# 1_-_MCU.net
KiCad netlist of a schematic drawn in Altium Designer
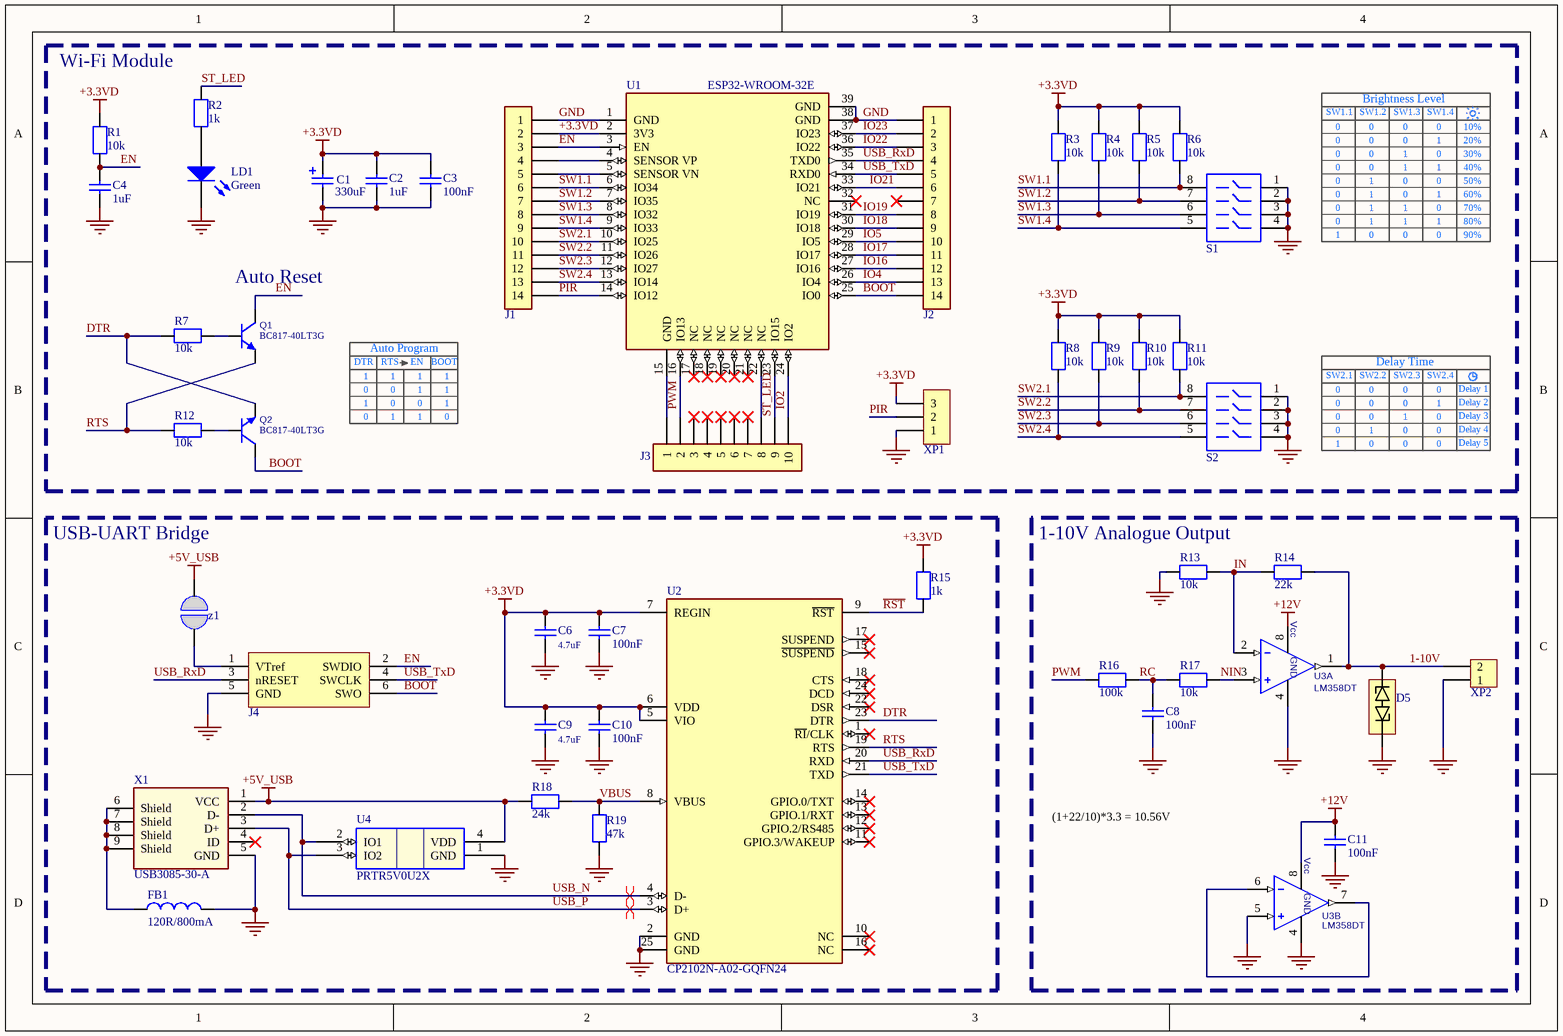
[diagram p0: [1] - MCU.SchDoc]

(export (version "E")
  (design (tool "Eeschema 10.0.6"))
  (components
    (comp (ref "C1")
      (value "330uF")
      (footprint "TANT CAP CASE B")
      (description "Surface Mount Tantalum Capacitor, 330 µF, 6.3 V, 1411 [3528 Metric], ± 20%, 0.8 ohm, B")
      (fields (field (name "TOLERANCE") "+/-20%") (field (name "MANUFACTURER") "KEMET"))
      (libsource (lib "YAQF") (part "Capacitors_SMD_TANT"))
    )
    (comp (ref "C2")
      (value "1uF")
      (footprint "CC0603")
      (description "SMD Multilayer Ceramic Capacitor, 1 µF, 16 V, 0603 [1608 Metric], ± 10%, X7R, MC")
      (fields
        (field (name "MANUFACTURER") "MULTICOMP")
        (field (name "MANUFACTURER PART NUMBER") "MC0603B105K160CT")
      )
      (libsource (lib "YAQF") (part "Capacitors_SMD"))
    )
    (comp (ref "C3")
      (value "100nF")
      (footprint "CC0603")
      (description "SMD Multilayer Ceramic Capacitor, 0.1 µF, 16 V, 0603 [1608 Metric], ± 10%, X7R, MC")
      (fields
        (field (name "MANUFACTURER") "MULTICOMP")
        (field (name "MANUFACTURER PART NUMBER") "MC0603B104K160CT")
      )
      (libsource (lib "YAQF") (part "Capacitors_SMD"))
    )
    (comp (ref "C4")
      (value "1uF")
      (footprint "CC0603")
      (description "SMD Multilayer Ceramic Capacitor, 1 µF, 16 V, 0603 [1608 Metric], ± 10%, X7R, MC")
      (fields
        (field (name "MANUFACTURER") "MULTICOMP")
        (field (name "MANUFACTURER PART NUMBER") "MC0603B105K160CT")
      )
      (libsource (lib "YAQF") (part "Capacitors_SMD"))
    )
    (comp (ref "C6")
      (value "4.7uF")
      (footprint "CC0603")
      (description "SMD Multilayer Ceramic Capacitor, 4.7 µF, 6.3 V, 0603 [1608 Metric], ± 10%, X7R, CL")
      (fields
        (field (name "MANUFACTURER") "SAMSUNG ELECTRO-MECHANICS")
        (field (name "MANUFACTURER PART NUMBER") "CL10B475KQ8NQNC")
      )
      (libsource (lib "ENEL004.201.001") (part "Capacitors_SMD_10"))
    )
    (comp (ref "C7")
      (value "100nF")
      (footprint "CC0603")
      (description "SMD Multilayer Ceramic Capacitor, 0.1 µF, 16 V, 0603 [1608 Metric], ± 10%, X7R, MC")
      (fields
        (field (name "MANUFACTURER") "MULTICOMP")
        (field (name "MANUFACTURER PART NUMBER") "MC0603B104K160CT")
      )
      (libsource (lib "YAQF") (part "Capacitors_SMD"))
    )
    (comp (ref "C8")
      (value "100nF")
      (footprint "CC0603")
      (description "SMD Multilayer Ceramic Capacitor, 0.1 µF, 16 V, 0603 [1608 Metric], ± 10%, X7R, MC")
      (fields
        (field (name "MANUFACTURER") "MULTICOMP")
        (field (name "MANUFACTURER PART NUMBER") "MC0603B104K160CT")
      )
      (libsource (lib "YAQF") (part "Capacitors_SMD"))
    )
    (comp (ref "C9")
      (value "4.7uF")
      (footprint "CC0603")
      (description "SMD Multilayer Ceramic Capacitor, 4.7 µF, 6.3 V, 0603 [1608 Metric], ± 10%, X7R, CL")
      (fields
        (field (name "MANUFACTURER") "SAMSUNG ELECTRO-MECHANICS")
        (field (name "MANUFACTURER PART NUMBER") "CL10B475KQ8NQNC")
      )
      (libsource (lib "ENEL004.201.001") (part "Capacitors_SMD_10"))
    )
    (comp (ref "C10")
      (value "100nF")
      (footprint "CC0603")
      (description "SMD Multilayer Ceramic Capacitor, 0.1 µF, 16 V, 0603 [1608 Metric], ± 10%, X7R, MC")
      (fields
        (field (name "MANUFACTURER") "MULTICOMP")
        (field (name "MANUFACTURER PART NUMBER") "MC0603B104K160CT")
      )
      (libsource (lib "YAQF") (part "Capacitors_SMD"))
    )
    (comp (ref "C11")
      (value "100nF")
      (footprint "CC0603")
      (description "SMD Multilayer Ceramic Capacitor, 0.1 µF, 16 V, 0603 [1608 Metric], ± 10%, X7R, MC")
      (fields
        (field (name "MANUFACTURER") "MULTICOMP")
        (field (name "MANUFACTURER PART NUMBER") "MC0603B104K160CT")
      )
      (libsource (lib "YAQF") (part "Capacitors_SMD"))
    )
    (comp (ref "D5")
      (value "CDSOD323-T12SC")
      (footprint "SOD323")
      (description "TVS DIODE 12VWM 29.5VC SOD323")
      (fields
        (field (name "VOLTAGE") "12V")
        (field (name "MANUFACTURER") "Bourns")
        (field (name "PUBLISHER") "dlehkobyt")
      )
      (libsource (lib "Aldiva_Altium_Library") (part "PESDXVL1BA"))
    )
    (comp (ref "FB1")
      (value "120R/800mA")
      (footprint "ind0603")
      (description "Ferrite Bead, 0603 [1608 Metric], 120 ohm, 800 mA, BLM18AG, 0.18 ohm, ± 25%")
      (fields
        (field (name "MANUFACTURER") "Murata Electronics")
        (field (name "MANUFACTURER PART NUMBER") "BLM18AG121BH1D")
      )
      (libsource (lib "YAQF") (part "Inductor_SMD"))
    )
    (comp (ref "J1")
      (value "TMS-114-02-L-S")
      (footprint "1-10V_PIR_V1.0:TMS-114-YY-XX-S")
      (description "Pin Header, Vertical, Board-to-Board, 1.27 mm, 1 Rows, 14 Contacts, Through Hole, TMS")
      (fields (field (name "MANUFACTURER") "SAMTEC") (field (name "MOUSER PART NUMBER") "200-TMS11402LS"))
      (libsource (lib "1-10V_PIR_V1.0") (part "TMS-114-02-L-S"))
    )
    (comp (ref "J2")
      (value "TMS-114-02-L-S")
      (footprint "1-10V_PIR_V1.0:TMS-114-YY-XX-S")
      (description "Pin Header, Vertical, Board-to-Board, 1.27 mm, 1 Rows, 14 Contacts, Through Hole, TMS")
      (fields (field (name "MANUFACTURER") "SAMTEC") (field (name "MOUSER PART NUMBER") "200-TMS11402LS"))
      (libsource (lib "") (part "TMS-114-02-L-S_1"))
    )
    (comp (ref "J3")
      (value "TMS-110-02-L-S")
      (footprint "SAMTEC_TMS-110-02-L-S")
      (description "Pin Header, Vertical, Board-to-Board, 1.27 mm, 1 Rows, 10 Contacts, Through Hole, TMS")
      (fields (field (name "MANUFACTURER") "SAMTEC"))
      (libsource (lib "1-10V_PIR_V1.0") (part "TMS-110-02-L-S"))
    )
    (comp (ref "J4")
      (value "TC2030-IDC")
      (footprint "TC2030-IDC")
      (description "TC2030-IDC 6-Pin Tag-Connect Plug-of-Nails™ Spring-Pin Cable with Legs")
      (libsource (lib "1-10V_PIR_V1.0") (part "TC2030-IDC"))
    )
    (comp (ref "LD1")
      (value "LED")
      (footprint "LED0603")
      (description "LED GREEN 0603 SMD")
      (fields
        (field (name "PART NUMBER") "TLMG1100-GS08")
        (field (name "COLOR") "Green")
        (field (name "VOLTAGE") "2.1V")
        (field (name "PUBLISHER") "asavchenko")
      )
      (libsource (lib "Aldiva_Altium_Library") (part "LED"))
    )
    (comp (ref "Q1")
      (value "BC817-40LT3G")
      (footprint "SOT23-3")
      (description "TRANS NPN 45V 0.5A SOT23")
      (fields (field (name "PART NUMBER") "BC817-40LT3G") (field (name "MANUFACTURER") "ONS, NXP"))
      (libsource (lib "Aldiva_Altium_Library") (part "NPN_transistor_SOT23-3"))
    )
    (comp (ref "Q2")
      (value "BC817-40LT3G")
      (footprint "SOT23-3")
      (description "TRANS NPN 45V 0.5A SOT23")
      (fields (field (name "PART NUMBER") "BC817-40LT3G") (field (name "MANUFACTURER") "ONS, NXP"))
      (libsource (lib "Aldiva_Altium_Library") (part "NPN_transistor_SOT23-3"))
    )
    (comp (ref "R1")
      (value "10k")
      (footprint "RC0603")
      (description "SMD Chip Resistor, 10 kohm, ± 1%, 100 mW, 0603 [1608 Metric], Thick Film, General Purpose")
      (fields
        (field (name "MANUFACTURER") "MULTICOMP")
        (field (name "MANUFACTURER PART NUMBER") "MCWR06X1002FTL")
      )
      (libsource (lib "") (part "Resistors_SMD_1"))
    )
    (comp (ref "R2")
      (value "1k")
      (footprint "RC0603")
      (description "SMD Chip Resistor, 1 kohm, ± 1%, 100 mW, 0603 [1608 Metric], Thick Film, General Purpose")
      (fields
        (field (name "MANUFACTURER") "MULTICOMP")
        (field (name "MANUFACTURER PART NUMBER") "MCWR06X1001FTL")
      )
      (libsource (lib "ENEL004.201.001") (part "Resistors_SMD"))
    )
    (comp (ref "R3")
      (value "10k")
      (footprint "RC0603")
      (description "SMD Chip Resistor, 10 kohm, ± 1%, 100 mW, 0603 [1608 Metric], Thick Film, General Purpose")
      (fields
        (field (name "MANUFACTURER") "MULTICOMP")
        (field (name "MANUFACTURER PART NUMBER") "MCWR06X1002FTL")
      )
      (libsource (lib "") (part "Resistors_SMD_1"))
    )
    (comp (ref "R4")
      (value "10k")
      (footprint "RC0603")
      (description "SMD Chip Resistor, 10 kohm, ± 1%, 100 mW, 0603 [1608 Metric], Thick Film, General Purpose")
      (fields
        (field (name "MANUFACTURER") "MULTICOMP")
        (field (name "MANUFACTURER PART NUMBER") "MCWR06X1002FTL")
      )
      (libsource (lib "") (part "Resistors_SMD_1"))
    )
    (comp (ref "R5")
      (value "10k")
      (footprint "RC0603")
      (description "SMD Chip Resistor, 10 kohm, ± 1%, 100 mW, 0603 [1608 Metric], Thick Film, General Purpose")
      (fields
        (field (name "MANUFACTURER") "MULTICOMP")
        (field (name "MANUFACTURER PART NUMBER") "MCWR06X1002FTL")
      )
      (libsource (lib "") (part "Resistors_SMD_1"))
    )
    (comp (ref "R6")
      (value "10k")
      (footprint "RC0603")
      (description "SMD Chip Resistor, 10 kohm, ± 1%, 100 mW, 0603 [1608 Metric], Thick Film, General Purpose")
      (fields
        (field (name "MANUFACTURER") "MULTICOMP")
        (field (name "MANUFACTURER PART NUMBER") "MCWR06X1002FTL")
      )
      (libsource (lib "") (part "Resistors_SMD_1"))
    )
    (comp (ref "R7")
      (value "10k")
      (footprint "RC0603")
      (description "SMD Chip Resistor, 10 kohm, ± 1%, 100 mW, 0603 [1608 Metric], Thick Film, General Purpose")
      (fields
        (field (name "MANUFACTURER") "MULTICOMP")
        (field (name "MANUFACTURER PART NUMBER") "MCWR06X1002FTL")
      )
      (libsource (lib "") (part "Resistors_SMD_2"))
    )
    (comp (ref "R8")
      (value "10k")
      (footprint "RC0603")
      (description "SMD Chip Resistor, 10 kohm, ± 1%, 100 mW, 0603 [1608 Metric], Thick Film, General Purpose")
      (fields
        (field (name "MANUFACTURER") "MULTICOMP")
        (field (name "MANUFACTURER PART NUMBER") "MCWR06X1002FTL")
      )
      (libsource (lib "") (part "Resistors_SMD_1"))
    )
    (comp (ref "R9")
      (value "10k")
      (footprint "RC0603")
      (description "SMD Chip Resistor, 10 kohm, ± 1%, 100 mW, 0603 [1608 Metric], Thick Film, General Purpose")
      (fields
        (field (name "MANUFACTURER") "MULTICOMP")
        (field (name "MANUFACTURER PART NUMBER") "MCWR06X1002FTL")
      )
      (libsource (lib "") (part "Resistors_SMD_1"))
    )
    (comp (ref "R10")
      (value "10k")
      (footprint "RC0603")
      (description "SMD Chip Resistor, 10 kohm, ± 1%, 100 mW, 0603 [1608 Metric], Thick Film, General Purpose")
      (fields
        (field (name "MANUFACTURER") "MULTICOMP")
        (field (name "MANUFACTURER PART NUMBER") "MCWR06X1002FTL")
      )
      (libsource (lib "") (part "Resistors_SMD_1"))
    )
    (comp (ref "R11")
      (value "10k")
      (footprint "RC0603")
      (description "SMD Chip Resistor, 10 kohm, ± 1%, 100 mW, 0603 [1608 Metric], Thick Film, General Purpose")
      (fields
        (field (name "MANUFACTURER") "MULTICOMP")
        (field (name "MANUFACTURER PART NUMBER") "MCWR06X1002FTL")
      )
      (libsource (lib "") (part "Resistors_SMD_1"))
    )
    (comp (ref "R12")
      (value "10k")
      (footprint "RC0603")
      (description "SMD Chip Resistor, 10 kohm, ± 1%, 100 mW, 0603 [1608 Metric], Thick Film, General Purpose")
      (fields
        (field (name "MANUFACTURER") "MULTICOMP")
        (field (name "MANUFACTURER PART NUMBER") "MCWR06X1002FTL")
      )
      (libsource (lib "") (part "Resistors_SMD_2"))
    )
    (comp (ref "R13")
      (value "10k")
      (footprint "RC0603")
      (description "SMD Chip Resistor, 10 kohm, ± 1%, 100 mW, 0603 [1608 Metric], Thick Film, General Purpose")
      (fields
        (field (name "MANUFACTURER") "MULTICOMP")
        (field (name "MANUFACTURER PART NUMBER") "MCWR06X1002FTL")
      )
      (libsource (lib "YAQF") (part "Resistors_SMD"))
    )
    (comp (ref "R14")
      (value "22k")
      (footprint "RC0603")
      (description "SMD Chip Resistor, 22 kohm, ± 1%, 100 mW, 0603 [1608 Metric], Thick Film, General Purpose")
      (fields
        (field (name "MANUFACTURER") "MULTICOMP")
        (field (name "MANUFACTURER PART NUMBER") "MCWR06X2202FTL")
      )
      (libsource (lib "YAQF") (part "Resistors_SMD"))
    )
    (comp (ref "R15")
      (value "1k")
      (footprint "RC0603")
      (description "SMD Chip Resistor, 1 kohm, ± 1%, 100 mW, 0603 [1608 Metric], Thick Film, General Purpose")
      (fields
        (field (name "MANUFACTURER") "MULTICOMP")
        (field (name "MANUFACTURER PART NUMBER") "MCWR06X1001FTL")
      )
      (libsource (lib "ENEL004.201.001") (part "Resistors_SMD"))
    )
    (comp (ref "R16")
      (value "100k")
      (footprint "RC0603")
      (description "SMD Chip Resistor, 100 kohm, ± 1%, 100 mW, 0603 [1608 Metric], Thick Film, General Purpose")
      (fields
        (field (name "MANUFACTURER") "MULTICOMP")
        (field (name "MANUFACTURER PART NUMBER") "MCWR06X1003FTL")
      )
      (libsource (lib "ENEL004.201.001") (part "Resistors_SMD_4"))
    )
    (comp (ref "R17")
      (value "10k")
      (footprint "RC0603")
      (description "SMD Chip Resistor, 10 kohm, ± 1%, 100 mW, 0603 [1608 Metric], Thick Film, General Purpose")
      (fields
        (field (name "MANUFACTURER") "MULTICOMP")
        (field (name "MANUFACTURER PART NUMBER") "MCWR06X1002FTL")
      )
      (libsource (lib "") (part "Resistors_SMD_2"))
    )
    (comp (ref "R18")
      (value "24k")
      (footprint "RC0603")
      (description "SMD Chip Resistor, 24 kohm, ± 1%, 100 mW, 0603 [1608 Metric], Thick Film, General Purpose")
      (fields
        (field (name "MANUFACTURER") "MULTICOMP")
        (field (name "MANUFACTURER PART NUMBER") "MCWR06X2402FTL")
      )
      (libsource (lib "") (part "Resistors_SMD_24_1"))
    )
    (comp (ref "R19")
      (value "47k")
      (footprint "RC0603")
      (description "SMD Chip Resistor, 47 kohm, ± 1%, 100 mW, 0603 [1608 Metric], Thick Film, General Purpose")
      (fields
        (field (name "MANUFACTURER") "MULTICOMP")
        (field (name "MANUFACTURER PART NUMBER") "MCWR06X4702FTL")
      )
      (libsource (lib "ENEL004.201.001") (part "Resistors_SMD_24"))
    )
    (comp (ref "S1")
      (value "SW-DIP4")
      (footprint "SW-DIP-8")
      (description "DIP / SIP Switch, 4 Circuits, Raised Slide, Through Hole, SPST-NO, 24 V, 25 mA")
      (fields (field (name "PART NUMBER") "MCNDS-04V") (field (name "MANUFACTURER") "MULTICOMP PRO"))
      (libsource (lib "1-10V_PIR_V1.0") (part "SW-DIP4"))
    )
    (comp (ref "S2")
      (value "SW-DIP4")
      (footprint "SW-DIP-8")
      (description "DIP / SIP Switch, 4 Circuits, Raised Slide, Through Hole, SPST-NO, 24 V, 25 mA")
      (fields (field (name "PART NUMBER") "MCNDS-04V") (field (name "MANUFACTURER") "MULTICOMP PRO"))
      (libsource (lib "1-10V_PIR_V1.0") (part "SW-DIP4"))
    )
    (comp (ref "U1")
      (value "ESP32-WROOM-32E")
      (footprint "ESP32-WROOM-32E-Footprint-1")
      (fields
        (field (name "MANUFACTURER") "Espressif Systems")
        (field (name "MANUFACTURER PART NUMBER") "ESP32-WROOM-32E-N16")
      )
      (libsource (lib "1-10V_PIR_V1.0") (part "ESP32-WROOM-32E"))
    )
    (comp (ref "U2")
      (value "CP2102N-A02-GQFN24")
      (footprint "Components - 17.11.22 - 15.18:FP-CP2102N-A02-GQFN24-MFG")
      (description "IC USB TO UART BRIDGE QFN24")
      (fields (field (name "MANUFACTURER") "Silabs"))
      (libsource (lib "3PHPowerMeter_V1.0") (part "CMP-08107-000010-1"))
    )
    (comp (ref "U3")
      (value "LM358DT")
      (footprint "SO-8")
      (description "Operational Amplifier, Dual, 2 Amplifier, 1.1 MHz, 0.6 V/µs, 3V to 30V, SOIC, 8 Pins")
      (fields (field (name "MANUFACTURER") "STMICROELECTRONICS"))
      (libsource (lib "1-10V_PIR_V1.0") (part "LM358DT"))
    )
    (comp (ref "U4")
      (value "PRTR5V0U2X")
      (footprint "SOT190P230X110-4L")
      (description "ESD Protection Device, TVS, 7.5 V, SOT-143B, 4 Pins, 5.5 V, PRTR5")
      (fields (field (name "MANUFACTURER") "NXP Semiconductor"))
      (libsource (lib "YAQF") (part "PRTR5V0U2X_Protect"))
    )
    (comp (ref "X1")
      (value "USB3085-30-A")
      (footprint "USB3085-30-A")
      (description "USB Connector, Micro USB Type AB, USB 2.0, Receptacle, 5 Ways, Surface Mount, Right Angle")
      (fields (field (name "MANUFACTURER") "GTC"))
      (libsource (lib "1-10V_PIR_V1.0") (part "USB3085-30-A"))
    )
    (comp (ref "XP1")
      (value "Header 3x1pins")
      (footprint "MC 1,5_3-G-3,81")
      (description "Terminal Block, Header, 3.81 mm, 3 Ways, 8 A, 160 V, Through Hole Right Angle")
      (fields
        (field (name "PART NUMBER") "MC 1,5/ 3-G-3,81")
        (field (name "MANUFACTURER") "PHOENIX CONTACT")
        (field (name "PUBLISHER") "dlegkobyt")
      )
      (libsource (lib "Aldiva_Altium_Library") (part "Header 3x1pins"))
    )
    (comp (ref "XP2")
      (value "Header 2x1pins")
      (footprint "MC 1,5_2-G-3,81")
      (description "Terminal Block, Header, 3.81 mm, 2 Ways, 8 A, 160 V, Through Hole Right Angle")
      (fields
        (field (name "PART NUMBER") "MC 1,5/ 2-G-3,81")
        (field (name "MANUFACTURER") "PHOENIX CONTACT")
        (field (name "PUBLISHER") "dlegkobyt")
      )
      (libsource (lib "Aldiva_Altium_Library") (part "Header 2x1pins"))
    )
    (comp (ref "z1")
      (value "SHORT")
      (footprint "PAD_JUMPER")
      (libsource (lib "1-10V_PIR_V1.0") (part "JUMPER_OPEN"))
    )
  )
  (nets
    (net (code "1") (name "+3.3VD") (class "Default")
      (node (ref "C1") (pin "1") (pinfunction "1_1") (pintype "passive"))
      (node (ref "C10") (pin "1") (pinfunction "1_1") (pintype "passive"))
      (node (ref "C2") (pin "1") (pinfunction "1_1") (pintype "passive"))
      (node (ref "C3") (pin "1") (pinfunction "1_1") (pintype "passive"))
      (node (ref "C6") (pin "1") (pinfunction "1_1") (pintype "passive"))
      (node (ref "C7") (pin "1") (pinfunction "1_1") (pintype "passive"))
      (node (ref "C9") (pin "1") (pinfunction "1_1") (pintype "passive"))
      (node (ref "J1") (pin "2") (pinfunction "2_2") (pintype "passive"))
      (node (ref "R1") (pin "2") (pinfunction "2_2") (pintype "passive"))
      (node (ref "R10") (pin "2") (pinfunction "2_2") (pintype "passive"))
      (node (ref "R11") (pin "2") (pinfunction "2_2") (pintype "passive"))
      (node (ref "R15") (pin "2") (pinfunction "2_2") (pintype "passive"))
      (node (ref "R3") (pin "2") (pinfunction "2_2") (pintype "passive"))
      (node (ref "R4") (pin "2") (pinfunction "2_2") (pintype "passive"))
      (node (ref "R5") (pin "2") (pinfunction "2_2") (pintype "passive"))
      (node (ref "R6") (pin "2") (pinfunction "2_2") (pintype "passive"))
      (node (ref "R8") (pin "2") (pinfunction "2_2") (pintype "passive"))
      (node (ref "R9") (pin "2") (pinfunction "2_2") (pintype "passive"))
      (node (ref "U1") (pin "2") (pinfunction "3V3_2") (pintype "power_in"))
      (node (ref "U2") (pin "5") (pinfunction "VIO_5") (pintype "power_in"))
      (node (ref "U2") (pin "6") (pinfunction "VDD_6") (pintype "power_in"))
      (node (ref "U2") (pin "7") (pinfunction "REGIN_7") (pintype "power_in"))
      (node (ref "XP1") (pin "3") (pinfunction "3_3") (pintype "passive"))
    )
    (net (code "2") (name "+5V_USB") (class "Default")
      (node (ref "R18") (pin "2") (pinfunction "2_2") (pintype "passive"))
      (node (ref "U4") (pin "4") (pinfunction "VDD_4") (pintype "power_in"))
      (node (ref "X1") (pin "1") (pinfunction "VCC_1") (pintype "passive"))
      (node (ref "z1") (pin "1") (pintype "passive"))
    )
    (net (code "3") (name "+12V") (class "Default")
      (node (ref "C11") (pin "1") (pinfunction "1_1") (pintype "passive"))
      (node (ref "U3") (pin "8") (pinfunction "Vcc_8") (pintype "power_in"))
    )
    (net (code "4") (name "/1-10V") (class "Default")
      (node (ref "D5") (pin "1") (pinfunction "P1_1") (pintype "passive"))
      (node (ref "R14") (pin "2") (pinfunction "2_2") (pintype "passive"))
      (node (ref "U3") (pin "1") (pinfunction "OUT1_1") (pintype "output"))
      (node (ref "XP2") (pin "2") (pinfunction "2_2") (pintype "passive"))
    )
    (net (code "5") (name "/BOOT") (class "Default")
      (node (ref "J2") (pin "14") (pinfunction "14_14") (pintype "passive"))
      (node (ref "J4") (pin "6") (pinfunction "SWO_6") (pintype "passive"))
      (node (ref "Q2") (pin "3") (pinfunction "C_3") (pintype "passive"))
      (node (ref "U1") (pin "25") (pinfunction "IO0_25") (pintype "bidirectional"))
    )
    (net (code "6") (name "/DTR") (class "Default")
      (node (ref "Q2") (pin "2") (pinfunction "E_2") (pintype "passive"))
      (node (ref "R7") (pin "2") (pinfunction "2_2") (pintype "passive"))
      (node (ref "U2") (pin "23") (pinfunction "DTR_23") (pintype "output"))
    )
    (net (code "7") (name "/EN") (class "Default")
      (node (ref "C4") (pin "1") (pinfunction "1_1") (pintype "passive"))
      (node (ref "J1") (pin "3") (pinfunction "3_3") (pintype "passive"))
      (node (ref "J4") (pin "2") (pinfunction "SWDIO_2") (pintype "passive"))
      (node (ref "Q1") (pin "3") (pinfunction "C_3") (pintype "passive"))
      (node (ref "R1") (pin "1") (pinfunction "1_1") (pintype "passive"))
      (node (ref "U1") (pin "3") (pinfunction "EN_3") (pintype "input"))
    )
    (net (code "8") (name "/IN") (class "Default")
      (node (ref "R13") (pin "2") (pinfunction "2_2") (pintype "passive"))
      (node (ref "R14") (pin "1") (pinfunction "1_1") (pintype "passive"))
      (node (ref "U3") (pin "2") (pinfunction "IN1-_2") (pintype "input"))
    )
    (net (code "9") (name "/IO2") (class "Default")
      (node (ref "J3") (pin "10") (pinfunction "10_10") (pintype "passive"))
      (node (ref "U1") (pin "24") (pinfunction "IO2_24") (pintype "bidirectional"))
    )
    (net (code "10") (name "/IO4") (class "Default")
      (node (ref "J2") (pin "13") (pinfunction "13_13") (pintype "passive"))
      (node (ref "U1") (pin "26") (pinfunction "IO4_26") (pintype "bidirectional"))
    )
    (net (code "11") (name "/IO5") (class "Default")
      (node (ref "J2") (pin "10") (pinfunction "10_10") (pintype "passive"))
      (node (ref "U1") (pin "29") (pinfunction "IO5_29") (pintype "bidirectional"))
    )
    (net (code "12") (name "/IO16") (class "Default")
      (node (ref "J2") (pin "12") (pinfunction "12_12") (pintype "passive"))
      (node (ref "U1") (pin "27") (pinfunction "IO16_27") (pintype "bidirectional"))
    )
    (net (code "13") (name "/IO17") (class "Default")
      (node (ref "J2") (pin "11") (pinfunction "11_11") (pintype "passive"))
      (node (ref "U1") (pin "28") (pinfunction "IO17_28") (pintype "bidirectional"))
    )
    (net (code "14") (name "/IO18") (class "Default")
      (node (ref "J2") (pin "9") (pinfunction "9_9") (pintype "passive"))
      (node (ref "U1") (pin "30") (pinfunction "IO18_30") (pintype "bidirectional"))
    )
    (net (code "15") (name "/IO19") (class "Default")
      (node (ref "J2") (pin "8") (pinfunction "8_8") (pintype "passive"))
      (node (ref "U1") (pin "31") (pinfunction "IO19_31") (pintype "bidirectional"))
    )
    (net (code "16") (name "/IO21") (class "Default")
      (node (ref "J2") (pin "6") (pinfunction "6_6") (pintype "passive"))
      (node (ref "U1") (pin "33") (pinfunction "IO21_33") (pintype "bidirectional"))
    )
    (net (code "17") (name "/IO22") (class "Default")
      (node (ref "J2") (pin "3") (pinfunction "3_3") (pintype "passive"))
      (node (ref "U1") (pin "36") (pinfunction "IO22_36") (pintype "bidirectional"))
    )
    (net (code "18") (name "/IO23") (class "Default")
      (node (ref "J2") (pin "2") (pinfunction "2_2") (pintype "passive"))
      (node (ref "U1") (pin "37") (pinfunction "IO23_37") (pintype "bidirectional"))
    )
    (net (code "19") (name "/NIN") (class "Default")
      (node (ref "R17") (pin "1") (pinfunction "1_1") (pintype "passive"))
      (node (ref "U3") (pin "3") (pinfunction "IN1+_3") (pintype "input"))
    )
    (net (code "20") (name "/PIR") (class "Default")
      (node (ref "J1") (pin "14") (pinfunction "14_14") (pintype "passive"))
      (node (ref "U1") (pin "14") (pinfunction "IO12_14") (pintype "bidirectional"))
      (node (ref "XP1") (pin "2") (pinfunction "2_2") (pintype "passive"))
    )
    (net (code "21") (name "/PWM") (class "Default")
      (node (ref "J3") (pin "2") (pinfunction "2_2") (pintype "passive"))
      (node (ref "R16") (pin "1") (pinfunction "1_1") (pintype "passive"))
      (node (ref "U1") (pin "16") (pinfunction "IO13_16") (pintype "bidirectional"))
    )
    (net (code "22") (name "/RC") (class "Default")
      (node (ref "C8") (pin "1") (pinfunction "1_1") (pintype "passive"))
      (node (ref "R16") (pin "2") (pinfunction "2_2") (pintype "passive"))
      (node (ref "R17") (pin "2") (pinfunction "2_2") (pintype "passive"))
    )
    (net (code "23") (name "/RTS") (class "Default")
      (node (ref "Q1") (pin "2") (pinfunction "E_2") (pintype "passive"))
      (node (ref "R12") (pin "2") (pinfunction "2_2") (pintype "passive"))
      (node (ref "U2") (pin "19") (pinfunction "RTS_19") (pintype "output"))
    )
    (net (code "24") (name "/ST_LED") (class "Default")
      (node (ref "J3") (pin "9") (pinfunction "9_9") (pintype "passive"))
      (node (ref "R2") (pin "2") (pinfunction "2_2") (pintype "passive"))
      (node (ref "U1") (pin "23") (pinfunction "IO15_23") (pintype "bidirectional"))
    )
    (net (code "25") (name "/SW1.1") (class "Default")
      (node (ref "J1") (pin "6") (pinfunction "6_6") (pintype "passive"))
      (node (ref "R6") (pin "1") (pinfunction "1_1") (pintype "passive"))
      (node (ref "S1") (pin "8") (pinfunction "8_8") (pintype "passive"))
      (node (ref "U1") (pin "6") (pinfunction "IO34_6") (pintype "bidirectional"))
    )
    (net (code "26") (name "/SW1.2") (class "Default")
      (node (ref "J1") (pin "7") (pinfunction "7_7") (pintype "passive"))
      (node (ref "R5") (pin "1") (pinfunction "1_1") (pintype "passive"))
      (node (ref "S1") (pin "7") (pinfunction "7_7") (pintype "passive"))
      (node (ref "U1") (pin "7") (pinfunction "IO35_7") (pintype "bidirectional"))
    )
    (net (code "27") (name "/SW1.3") (class "Default")
      (node (ref "J1") (pin "8") (pinfunction "8_8") (pintype "passive"))
      (node (ref "R4") (pin "1") (pinfunction "1_1") (pintype "passive"))
      (node (ref "S1") (pin "6") (pinfunction "6_6") (pintype "passive"))
      (node (ref "U1") (pin "8") (pinfunction "IO32_8") (pintype "bidirectional"))
    )
    (net (code "28") (name "/SW1.4") (class "Default")
      (node (ref "J1") (pin "9") (pinfunction "9_9") (pintype "passive"))
      (node (ref "R3") (pin "1") (pinfunction "1_1") (pintype "passive"))
      (node (ref "S1") (pin "5") (pinfunction "5_5") (pintype "passive"))
      (node (ref "U1") (pin "9") (pinfunction "IO33_9") (pintype "bidirectional"))
    )
    (net (code "29") (name "/SW2.1") (class "Default")
      (node (ref "J1") (pin "10") (pinfunction "10_10") (pintype "passive"))
      (node (ref "R11") (pin "1") (pinfunction "1_1") (pintype "passive"))
      (node (ref "S2") (pin "8") (pinfunction "8_8") (pintype "passive"))
      (node (ref "U1") (pin "10") (pinfunction "IO25_10") (pintype "bidirectional"))
    )
    (net (code "30") (name "/SW2.2") (class "Default")
      (node (ref "J1") (pin "11") (pinfunction "11_11") (pintype "passive"))
      (node (ref "R10") (pin "1") (pinfunction "1_1") (pintype "passive"))
      (node (ref "S2") (pin "7") (pinfunction "7_7") (pintype "passive"))
      (node (ref "U1") (pin "11") (pinfunction "IO26_11") (pintype "bidirectional"))
    )
    (net (code "31") (name "/SW2.3") (class "Default")
      (node (ref "J1") (pin "12") (pinfunction "12_12") (pintype "passive"))
      (node (ref "R9") (pin "1") (pinfunction "1_1") (pintype "passive"))
      (node (ref "S2") (pin "6") (pinfunction "6_6") (pintype "passive"))
      (node (ref "U1") (pin "12") (pinfunction "IO27_12") (pintype "bidirectional"))
    )
    (net (code "32") (name "/SW2.4") (class "Default")
      (node (ref "J1") (pin "13") (pinfunction "13_13") (pintype "passive"))
      (node (ref "R8") (pin "1") (pinfunction "1_1") (pintype "passive"))
      (node (ref "S2") (pin "5") (pinfunction "5_5") (pintype "passive"))
      (node (ref "U1") (pin "13") (pinfunction "IO14_13") (pintype "bidirectional"))
    )
    (net (code "33") (name "/USB_N") (class "Default")
      (node (ref "U2") (pin "4") (pinfunction "D-_4") (pintype "bidirectional"))
      (node (ref "U4") (pin "2") (pinfunction "IO1_2") (pintype "bidirectional"))
      (node (ref "X1") (pin "2") (pinfunction "D-_2") (pintype "passive"))
    )
    (net (code "34") (name "/USB_P") (class "Default")
      (node (ref "U2") (pin "3") (pinfunction "D+_3") (pintype "bidirectional"))
      (node (ref "U4") (pin "3") (pinfunction "IO2_3") (pintype "bidirectional"))
      (node (ref "X1") (pin "3") (pinfunction "D+_3") (pintype "passive"))
    )
    (net (code "35") (name "/USB_RxD") (class "Default")
      (node (ref "J2") (pin "4") (pinfunction "4_4") (pintype "passive"))
      (node (ref "J4") (pin "3") (pinfunction "nRESET_3") (pintype "passive"))
      (node (ref "U1") (pin "35") (pinfunction "TXD0_35") (pintype "output"))
      (node (ref "U2") (pin "20") (pinfunction "RXD_20") (pintype "input"))
    )
    (net (code "36") (name "/USB_TxD") (class "Default")
      (node (ref "J2") (pin "5") (pinfunction "5_5") (pintype "passive"))
      (node (ref "J4") (pin "4") (pinfunction "SWCLK_4") (pintype "passive"))
      (node (ref "U1") (pin "34") (pinfunction "RXD0_34") (pintype "input"))
      (node (ref "U2") (pin "21") (pinfunction "TXD_21") (pintype "output"))
    )
    (net (code "37") (name "/VBUS") (class "Default")
      (node (ref "R18") (pin "1") (pinfunction "1_1") (pintype "passive"))
      (node (ref "R19") (pin "2") (pinfunction "2_2") (pintype "passive"))
      (node (ref "U2") (pin "8") (pinfunction "VBUS_8") (pintype "input"))
    )
    (net (code "38") (name "/~{RST}") (class "Default")
      (node (ref "R15") (pin "1") (pinfunction "1_1") (pintype "passive"))
      (node (ref "U2") (pin "9") (pinfunction "~{RST}_9") (pintype "passive"))
    )
    (net (code "39") (name "GND") (class "Default")
      (node (ref "C1") (pin "2") (pinfunction "2_2") (pintype "passive"))
      (node (ref "C10") (pin "2") (pinfunction "2_2") (pintype "passive"))
      (node (ref "C11") (pin "2") (pinfunction "2_2") (pintype "passive"))
      (node (ref "C2") (pin "2") (pinfunction "2_2") (pintype "passive"))
      (node (ref "C3") (pin "2") (pinfunction "2_2") (pintype "passive"))
      (node (ref "C4") (pin "2") (pinfunction "2_2") (pintype "passive"))
      (node (ref "C6") (pin "2") (pinfunction "2_2") (pintype "passive"))
      (node (ref "C7") (pin "2") (pinfunction "2_2") (pintype "passive"))
      (node (ref "C8") (pin "2") (pinfunction "2_2") (pintype "passive"))
      (node (ref "C9") (pin "2") (pinfunction "2_2") (pintype "passive"))
      (node (ref "D5") (pin "2") (pinfunction "P2_2") (pintype "passive"))
      (node (ref "FB1") (pin "1") (pinfunction "1_1") (pintype "passive"))
      (node (ref "J1") (pin "1") (pinfunction "1_1") (pintype "passive"))
      (node (ref "J2") (pin "1") (pinfunction "1_1") (pintype "passive"))
      (node (ref "J4") (pin "5") (pinfunction "GND_5") (pintype "passive"))
      (node (ref "LD1") (pin "1") (pinfunction "K_1") (pintype "passive"))
      (node (ref "R13") (pin "1") (pinfunction "1_1") (pintype "passive"))
      (node (ref "R19") (pin "1") (pinfunction "1_1") (pintype "passive"))
      (node (ref "S1") (pin "1") (pinfunction "1_1") (pintype "passive"))
      (node (ref "S1") (pin "2") (pinfunction "2_2") (pintype "passive"))
      (node (ref "S1") (pin "3") (pinfunction "3_3") (pintype "passive"))
      (node (ref "S1") (pin "4") (pinfunction "4_4") (pintype "passive"))
      (node (ref "S2") (pin "1") (pinfunction "1_1") (pintype "passive"))
      (node (ref "S2") (pin "2") (pinfunction "2_2") (pintype "passive"))
      (node (ref "S2") (pin "3") (pinfunction "3_3") (pintype "passive"))
      (node (ref "S2") (pin "4") (pinfunction "4_4") (pintype "passive"))
      (node (ref "U1") (pin "1") (pinfunction "GND_1") (pintype "power_in"))
      (node (ref "U1") (pin "38") (pinfunction "GND_38") (pintype "power_in"))
      (node (ref "U1") (pin "39") (pinfunction "GND_39") (pintype "power_in"))
      (node (ref "U2") (pin "2") (pinfunction "GND_2") (pintype "power_in"))
      (node (ref "U2") (pin "25") (pinfunction "GND_25") (pintype "power_in"))
      (node (ref "U3") (pin "4") (pinfunction "GND_4") (pintype "power_in"))
      (node (ref "U3") (pin "5") (pinfunction "IN2+_5") (pintype "input"))
      (node (ref "U4") (pin "1") (pinfunction "GND_1") (pintype "power_in"))
      (node (ref "X1") (pin "5") (pinfunction "GND_5") (pintype "passive"))
      (node (ref "XP1") (pin "1") (pinfunction "1_1") (pintype "passive"))
      (node (ref "XP2") (pin "1") (pinfunction "1_1") (pintype "passive"))
    )
    (net (code "40") (name "Net-(FB1-Pad2)") (class "Default")
      (node (ref "FB1") (pin "2") (pinfunction "2_2") (pintype "passive"))
      (node (ref "X1") (pin "6") (pinfunction "Shield_6") (pintype "passive"))
      (node (ref "X1") (pin "7") (pinfunction "Shield_7") (pintype "passive"))
      (node (ref "X1") (pin "8") (pinfunction "Shield_8") (pintype "passive"))
      (node (ref "X1") (pin "9") (pinfunction "Shield_9") (pintype "passive"))
    )
    (net (code "41") (name "Net-(J3-Pad1)") (class "Default")
      (node (ref "J3") (pin "1") (pinfunction "1_1") (pintype "passive"))
      (node (ref "U1") (pin "15") (pinfunction "GND_15") (pintype "power_in"))
    )
    (net (code "42") (name "Net-(J3-Pad8)") (class "Default")
      (node (ref "J3") (pin "8") (pinfunction "8_8") (pintype "passive"))
      (node (ref "U1") (pin "22") (pinfunction "NC_22") (pintype "bidirectional"))
    )
    (net (code "43") (name "Net-(J4-VTref)") (class "Default")
      (node (ref "J4") (pin "1") (pinfunction "VTref_1") (pintype "passive"))
      (node (ref "z1") (pin "2") (pintype "passive"))
    )
    (net (code "44") (name "Net-(LD1-A)") (class "Default")
      (node (ref "LD1") (pin "2") (pinfunction "A_2") (pintype "passive"))
      (node (ref "R2") (pin "1") (pinfunction "1_1") (pintype "passive"))
    )
    (net (code "45") (name "Net-(Q1-B)") (class "Default")
      (node (ref "Q1") (pin "1") (pinfunction "B_1") (pintype "passive"))
      (node (ref "R7") (pin "1") (pinfunction "1_1") (pintype "passive"))
    )
    (net (code "46") (name "Net-(Q2-B)") (class "Default")
      (node (ref "Q2") (pin "1") (pinfunction "B_1") (pintype "passive"))
      (node (ref "R12") (pin "1") (pinfunction "1_1") (pintype "passive"))
    )
    (net (code "47") (name "Net-(U1-SENSOR_VN)") (class "Default")
      (node (ref "J1") (pin "5") (pinfunction "5_5") (pintype "passive"))
      (node (ref "U1") (pin "5") (pinfunction "SENSOR_VN_5") (pintype "bidirectional"))
    )
    (net (code "48") (name "Net-(U1-SENSOR_VP)") (class "Default")
      (node (ref "J1") (pin "4") (pinfunction "4_4") (pintype "passive"))
      (node (ref "U1") (pin "4") (pinfunction "SENSOR_VP_4") (pintype "bidirectional"))
    )
    (net (code "49") (name "Net-(U3B-IN2-)") (class "Default")
      (node (ref "U3") (pin "6") (pinfunction "IN2-_6") (pintype "input"))
      (node (ref "U3") (pin "7") (pinfunction "OUT2_7") (pintype "output"))
    )
    (net (code "50") (name "unconnected-(J2-Pad7)") (class "Default")
      (node (ref "J2") (pin "7") (pinfunction "7_7") (pintype "passive+no_connect"))
    )
    (net (code "51") (name "unconnected-(J3-Pad3)") (class "Default")
      (node (ref "J3") (pin "3") (pinfunction "3_3") (pintype "passive+no_connect"))
    )
    (net (code "52") (name "unconnected-(J3-Pad4)") (class "Default")
      (node (ref "J3") (pin "4") (pinfunction "4_4") (pintype "passive+no_connect"))
    )
    (net (code "53") (name "unconnected-(J3-Pad5)") (class "Default")
      (node (ref "J3") (pin "5") (pinfunction "5_5") (pintype "passive+no_connect"))
    )
    (net (code "54") (name "unconnected-(J3-Pad6)") (class "Default")
      (node (ref "J3") (pin "6") (pinfunction "6_6") (pintype "passive+no_connect"))
    )
    (net (code "55") (name "unconnected-(J3-Pad7)") (class "Default")
      (node (ref "J3") (pin "7") (pinfunction "7_7") (pintype "passive+no_connect"))
    )
    (net (code "56") (name "unconnected-(U1-NC-Pad17)") (class "Default")
      (node (ref "U1") (pin "17") (pinfunction "NC_17") (pintype "bidirectional+no_connect"))
    )
    (net (code "57") (name "unconnected-(U1-NC-Pad18)") (class "Default")
      (node (ref "U1") (pin "18") (pinfunction "NC_18") (pintype "bidirectional+no_connect"))
    )
    (net (code "58") (name "unconnected-(U1-NC-Pad19)") (class "Default")
      (node (ref "U1") (pin "19") (pinfunction "NC_19") (pintype "bidirectional+no_connect"))
    )
    (net (code "59") (name "unconnected-(U1-NC-Pad20)") (class "Default")
      (node (ref "U1") (pin "20") (pinfunction "NC_20") (pintype "bidirectional+no_connect"))
    )
    (net (code "60") (name "unconnected-(U1-NC-Pad21)") (class "Default")
      (node (ref "U1") (pin "21") (pinfunction "NC_21") (pintype "bidirectional+no_connect"))
    )
    (net (code "61") (name "unconnected-(U1-NC-Pad32)") (class "Default")
      (node (ref "U1") (pin "32") (pinfunction "NC_32") (pintype "passive+no_connect"))
    )
    (net (code "62") (name "unconnected-(U2-CTS-Pad18)") (class "Default")
      (node (ref "U2") (pin "18") (pinfunction "CTS_18") (pintype "input+no_connect"))
    )
    (net (code "63") (name "unconnected-(U2-DCD-Pad24)") (class "Default")
      (node (ref "U2") (pin "24") (pinfunction "DCD_24") (pintype "input+no_connect"))
    )
    (net (code "64") (name "unconnected-(U2-DSR-Pad22)") (class "Default")
      (node (ref "U2") (pin "22") (pinfunction "DSR_22") (pintype "input+no_connect"))
    )
    (net (code "65") (name "unconnected-(U2-GPIO.0{slash}TXT-Pad14)") (class "Default")
      (node (ref "U2") (pin "14") (pinfunction "GPIO.0/TXT_14") (pintype "bidirectional+no_connect"))
    )
    (net (code "66") (name "unconnected-(U2-GPIO.1{slash}RXT-Pad13)") (class "Default")
      (node (ref "U2") (pin "13") (pinfunction "GPIO.1/RXT_13") (pintype "bidirectional+no_connect"))
    )
    (net (code "67") (name "unconnected-(U2-GPIO.2{slash}RS485-Pad12)") (class "Default")
      (node (ref "U2") (pin "12") (pinfunction "GPIO.2/RS485_12") (pintype "bidirectional+no_connect"))
    )
    (net (code "68") (name "unconnected-(U2-GPIO.3{slash}WAKEUP-Pad11)") (class "Default")
      (node (ref "U2") (pin "11") (pinfunction "GPIO.3/WAKEUP_11") (pintype "bidirectional+no_connect"))
    )
    (net (code "69") (name "unconnected-(U2-NC-Pad10)") (class "Default")
      (node (ref "U2") (pin "10") (pinfunction "NC_10") (pintype "passive+no_connect"))
    )
    (net (code "70") (name "unconnected-(U2-NC-Pad16)") (class "Default")
      (node (ref "U2") (pin "16") (pinfunction "NC_16") (pintype "passive+no_connect"))
    )
    (net (code "71") (name "unconnected-(U2-SUSPEND-Pad17)") (class "Default")
      (node (ref "U2") (pin "17") (pinfunction "SUSPEND_17") (pintype "output+no_connect"))
    )
    (net (code "72") (name "unconnected-(U2-~{RI}{slash}CLK-Pad1)") (class "Default")
      (node (ref "U2") (pin "1") (pinfunction "~{RI}/CLK_1") (pintype "bidirectional+no_connect"))
    )
    (net (code "73") (name "unconnected-(U2-~{SUSPEND}-Pad15)") (class "Default")
      (node (ref "U2") (pin "15") (pinfunction "~{SUSPEND}_15") (pintype "output+no_connect"))
    )
    (net (code "74") (name "unconnected-(X1-ID-Pad4)") (class "Default")
      (node (ref "X1") (pin "4") (pinfunction "ID_4") (pintype "passive+no_connect"))
    )
  )
)
